# sw_y.net
KiCad netlist of a schematic drawn in EAGLE
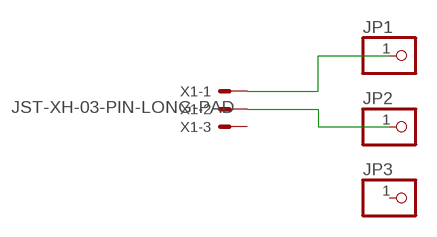
[diagram p0: schematic, sheet 1]

(export (version "E")
  (design (tool "Eeschema 10.0.6"))
  (components
    (comp (ref "JP1")
      (value "PINHD-1X1")
      (footprint "eagle-import:1X01")
      (libsource (lib "eagle-import") (part "PINHD-1X1"))
    )
    (comp (ref "JP2")
      (value "PINHD-1X1")
      (footprint "eagle-import:1X01")
      (libsource (lib "eagle-import") (part "PINHD-1X1"))
    )
    (comp (ref "JP3")
      (value "PINHD-1X1")
      (footprint "eagle-import:1X01")
      (libsource (lib "eagle-import") (part "PINHD-1X1"))
    )
    (comp (ref "X1")
      (value "JST-XH-03-PIN-LONG-PAD")
      (footprint "eagle-import:JST-XH-03-PACKAGE-LONG-PAD")
      (libsource (lib "eagle-import") (part "JST-XH-03-PIN-LONG-PAD"))
    )
  )
  (nets
    (net (code "1") (name "Net-(X1A-S)") (class "Default")
      (node (ref "JP1") (pin "1") (pinfunction "1_1") (pintype "passive"))
      (node (ref "X1") (pin "1") (pinfunction "S_1") (pintype "passive"))
    )
    (net (code "2") (name "Net-(X1B-S)") (class "Default")
      (node (ref "JP2") (pin "1") (pinfunction "1_1") (pintype "passive"))
      (node (ref "X1") (pin "2") (pinfunction "S_2") (pintype "passive"))
    )
    (net (code "3") (name "unconnected-(JP3-Pad1)") (class "Default")
      (node (ref "JP3") (pin "1") (pinfunction "1_1") (pintype "passive"))
    )
    (net (code "4") (name "unconnected-(X1C-S-Pad3)") (class "Default")
      (node (ref "X1") (pin "3") (pinfunction "S_3") (pintype "passive"))
    )
  )
)
